# SCH_NFC-Business-Card_2024-04-13.net
KiCad netlist of a schematic drawn in EasyEDA
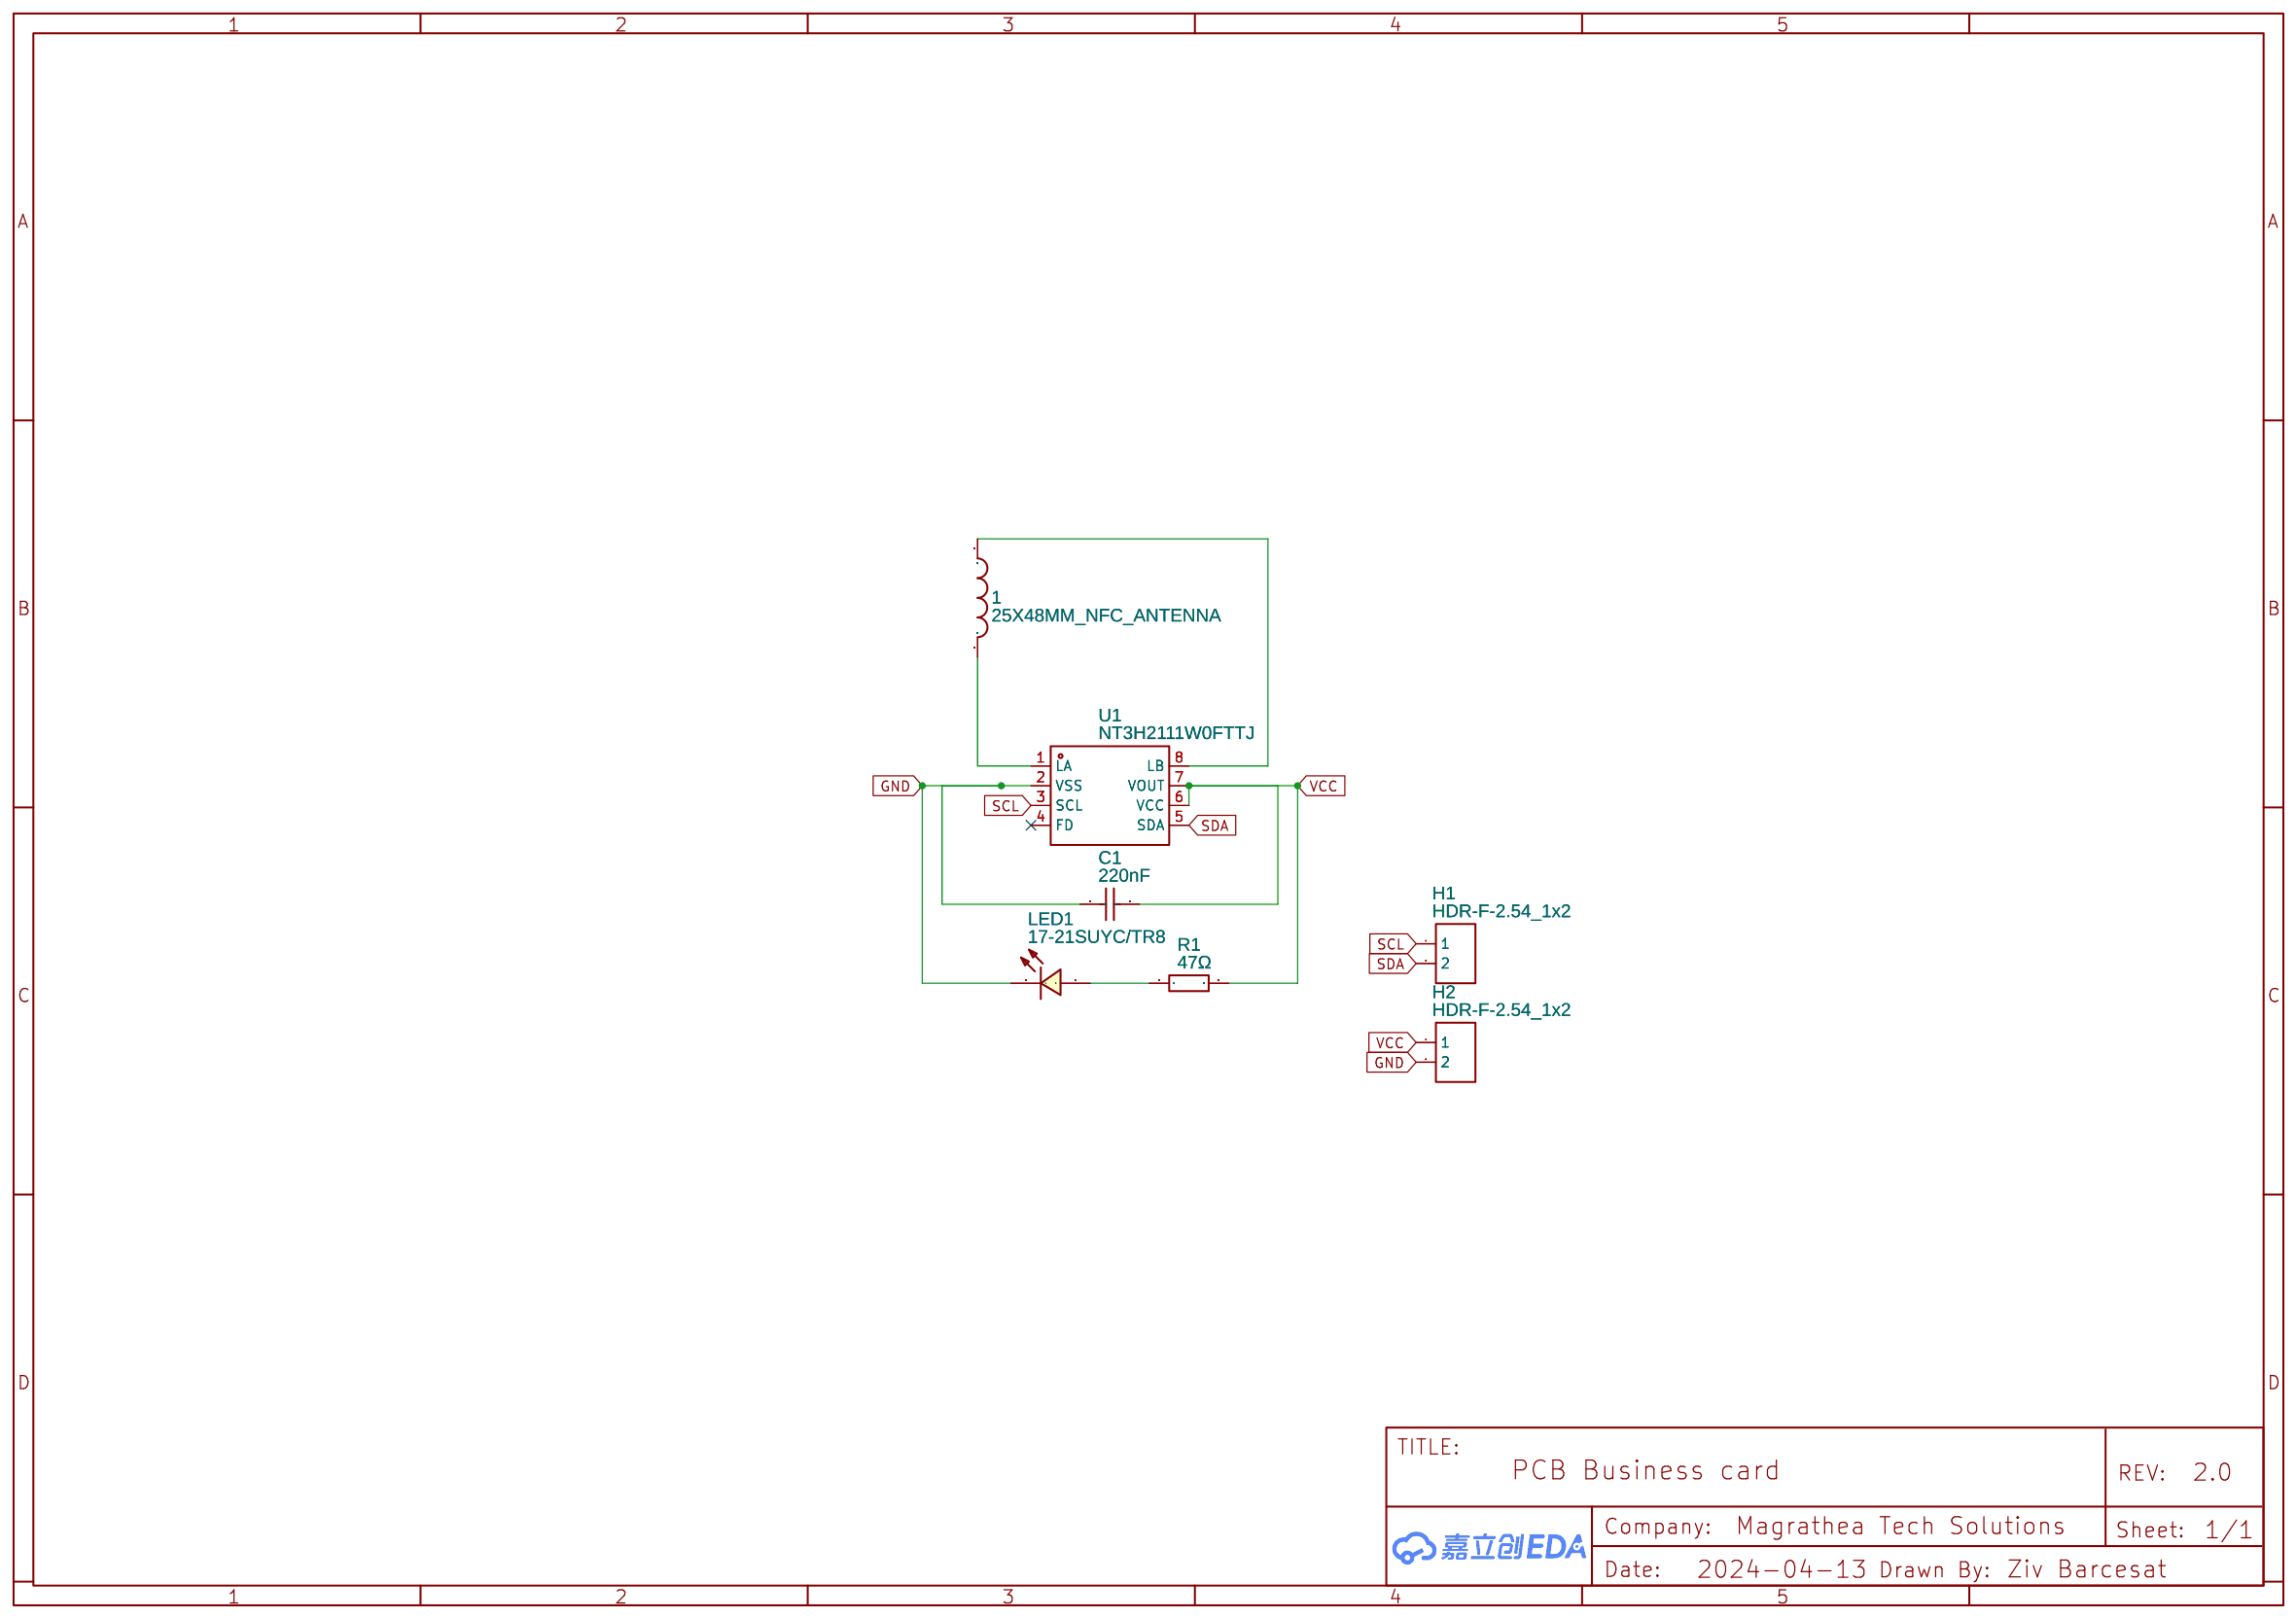
[diagram p0: schematic sheet]

(export (version "E")
  (design (tool "Eeschema 10.0.6"))
  (components
    (comp (ref "1") (value "25X48MM_NFC_ANTENNA") (libsource (lib "") (part "25X48MM_NFC_ANTENNA")))
    (comp (ref "C1")
      (value "220nF")
      (fields
        (field (name "Manufacturer Part") "CL10B224KA8NNNC")
        (field (name "Manufacturer") "SAMSUNG(三星)")
      )
      (libsource (lib "") (part "CL10B224KA8NNNC"))
    )
    (comp (ref "H1") (value "HDR-F-2.54_1x2") (libsource (lib "") (part "HDR-F-2.54_1x2")))
    (comp (ref "H2") (value "HDR-F-2.54_1x2") (libsource (lib "") (part "HDR-F-2.54_1x2")))
    (comp (ref "LED1")
      (value "17-21SUYC/TR8")
      (fields (field (name "Manufacturer Part") "KT-0805黄灯") (field (name "Manufacturer") "KENTO"))
      (libsource (lib "") (part "17-21SUYC/TR8"))
    )
    (comp (ref "R1")
      (value "47Ω")
      (fields
        (field (name "Manufacturer Part") "0603WAF470JT5E")
        (field (name "Manufacturer") "UNI-ROYAL(厚声)")
      )
      (libsource (lib "") (part "0603WAF470JT5E"))
    )
    (comp (ref "U1")
      (value "NT3H2111W0FTTJ")
      (fields (field (name "Manufacturer") "NXP(恩智浦)"))
      (libsource (lib "") (part "NT3H2111W0FTTJ"))
    )
  )
  (nets
    (net (code "1") (name "GND") (class "Default")
      (node (ref "C1") (pin "1") (pinfunction "1_1") (pintype "input"))
      (node (ref "H2") (pin "2") (pinfunction "2_2") (pintype "input"))
      (node (ref "LED1") (pin "2") (pinfunction "-_2") (pintype "unspecified"))
      (node (ref "U1") (pin "2") (pinfunction "VSS_2") (pintype "unspecified"))
    )
    (net (code "2") (name "Net-(LED1-+)") (class "Default")
      (node (ref "LED1") (pin "1") (pinfunction "+_1") (pintype "unspecified"))
      (node (ref "R1") (pin "1") (pinfunction "1_1") (pintype "input"))
    )
    (net (code "3") (name "Net-(U1-LA)") (class "Default")
      (node (ref "1") (pin "P$2") (pinfunction "P$2_P$2") (pintype "bidirectional"))
      (node (ref "U1") (pin "1") (pinfunction "LA_1") (pintype "unspecified"))
    )
    (net (code "4") (name "Net-(U1-LB)") (class "Default")
      (node (ref "1") (pin "P$1") (pinfunction "P$1_P$1") (pintype "bidirectional"))
      (node (ref "U1") (pin "8") (pinfunction "LB_8") (pintype "unspecified"))
    )
    (net (code "5") (name "SCL") (class "Default")
      (node (ref "H1") (pin "1") (pinfunction "1_1") (pintype "input"))
      (node (ref "U1") (pin "3") (pinfunction "SCL_3") (pintype "unspecified"))
    )
    (net (code "6") (name "SDA") (class "Default")
      (node (ref "H1") (pin "2") (pinfunction "2_2") (pintype "input"))
      (node (ref "U1") (pin "5") (pinfunction "SDA_5") (pintype "unspecified"))
    )
    (net (code "7") (name "VCC") (class "Default")
      (node (ref "C1") (pin "2") (pinfunction "2_2") (pintype "input"))
      (node (ref "H2") (pin "1") (pinfunction "1_1") (pintype "input"))
      (node (ref "R1") (pin "2") (pinfunction "2_2") (pintype "input"))
      (node (ref "U1") (pin "6") (pinfunction "VCC_6") (pintype "unspecified"))
      (node (ref "U1") (pin "7") (pinfunction "VOUT_7") (pintype "unspecified"))
    )
    (net (code "8") (name "unconnected-(U1-FD-Pad4)") (class "Default")
      (node (ref "U1") (pin "4") (pinfunction "FD_4") (pintype "unspecified+no_connect"))
    )
  )
)
